# FPGA.net
KiCad netlist of a schematic drawn in Altium Designer
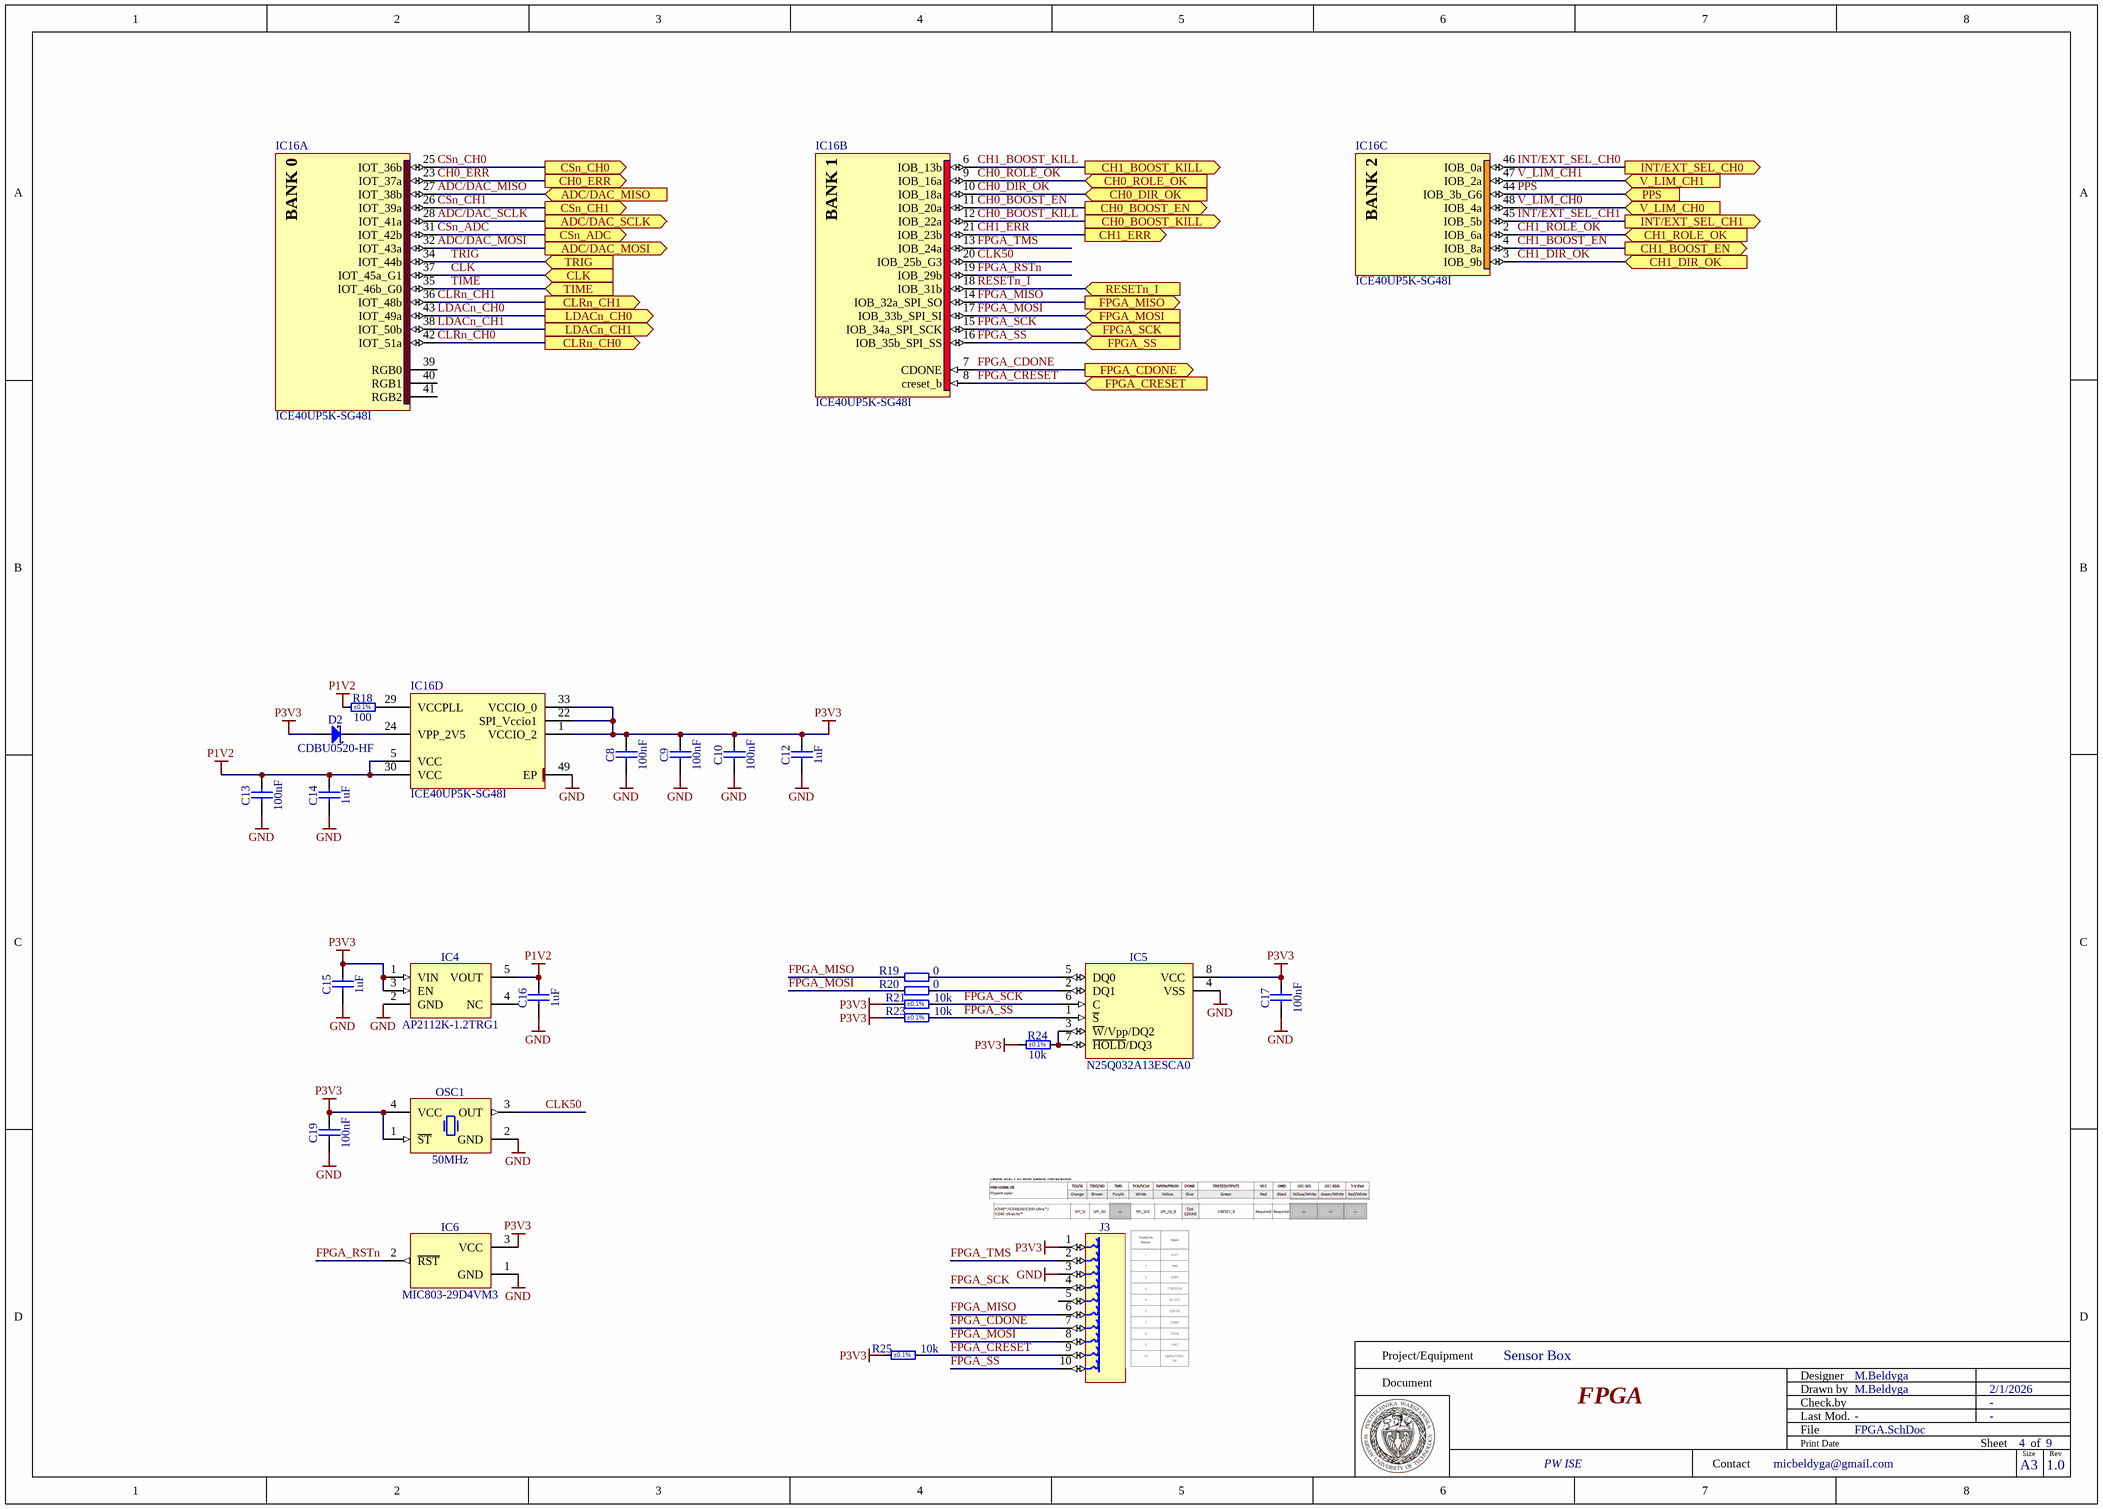
[diagram p0: FPGA.SchDoc]

(export (version "E")
  (design (tool "Eeschema 10.0.6"))
  (components
    (comp (ref "C8")
      (value "100nF")
      (footprint "CAPC1005X55N")
      (description "Non-polarised capacitor")
      (fields
        (field (name "PART NUMBER") "CC0402_100NF_16V_10%_X7R")
        (field (name "VOLTAGE") "16V")
        (field (name "AUTHOR") "CERN DEM JLC")
      )
      (libsource (lib "Capacitors") (part "Capacitor - non polarized"))
    )
    (comp (ref "C9")
      (value "100nF")
      (footprint "CAPC1005X55N")
      (description "Non-polarised capacitor")
      (fields
        (field (name "PART NUMBER") "CC0402_100NF_16V_10%_X7R")
        (field (name "VOLTAGE") "16V")
        (field (name "AUTHOR") "CERN DEM JLC")
      )
      (libsource (lib "Capacitors") (part "Capacitor - non polarized"))
    )
    (comp (ref "C10")
      (value "100nF")
      (footprint "CAPC1005X55N")
      (description "Non-polarised capacitor")
      (fields
        (field (name "PART NUMBER") "CC0402_100NF_16V_10%_X7R")
        (field (name "VOLTAGE") "16V")
        (field (name "AUTHOR") "CERN DEM JLC")
      )
      (libsource (lib "Capacitors") (part "Capacitor - non polarized"))
    )
    (comp (ref "C12")
      (value "1uF")
      (footprint "CAPC1005X55N")
      (description "Non-polarised capacitor")
      (fields
        (field (name "PART NUMBER") "CC0402_1UF_16V_10%_X5R")
        (field (name "VOLTAGE") "16V")
        (field (name "AUTHOR") "CERN DEM JLC")
      )
      (libsource (lib "Capacitors") (part "Capacitor - non polarized"))
    )
    (comp (ref "C13")
      (value "100nF")
      (footprint "CAPC1005X55N")
      (description "Non-polarised capacitor")
      (fields
        (field (name "PART NUMBER") "CC0402_100NF_16V_10%_X7R")
        (field (name "VOLTAGE") "16V")
        (field (name "AUTHOR") "CERN DEM JLC")
      )
      (libsource (lib "Capacitors") (part "Capacitor - non polarized"))
    )
    (comp (ref "C14")
      (value "1uF")
      (footprint "CAPC1005X55N")
      (description "Non-polarised capacitor")
      (fields
        (field (name "PART NUMBER") "CC0402_1UF_16V_10%_X5R")
        (field (name "VOLTAGE") "16V")
        (field (name "AUTHOR") "CERN DEM JLC")
      )
      (libsource (lib "Capacitors") (part "Capacitor - non polarized"))
    )
    (comp (ref "C15")
      (value "1uF")
      (footprint "CAPC1005X55N")
      (description "Non-polarised capacitor")
      (fields
        (field (name "PART NUMBER") "CC0402_1UF_16V_10%_X5R")
        (field (name "VOLTAGE") "16V")
        (field (name "AUTHOR") "CERN DEM JLC")
      )
      (libsource (lib "Capacitors") (part "Capacitor - non polarized"))
    )
    (comp (ref "C16")
      (value "1uF")
      (footprint "CAPC1005X55N")
      (description "Non-polarised capacitor")
      (fields
        (field (name "PART NUMBER") "CC0402_1UF_16V_10%_X5R")
        (field (name "VOLTAGE") "16V")
        (field (name "AUTHOR") "CERN DEM JLC")
      )
      (libsource (lib "Capacitors") (part "Capacitor - non polarized"))
    )
    (comp (ref "C17")
      (value "100nF")
      (footprint "CAPC1005X55N")
      (description "Non-polarised capacitor")
      (fields
        (field (name "PART NUMBER") "CC0402_100NF_16V_10%_X7R")
        (field (name "VOLTAGE") "16V")
        (field (name "AUTHOR") "CERN DEM JLC")
      )
      (libsource (lib "Capacitors") (part "Capacitor - non polarized"))
    )
    (comp (ref "C19")
      (value "100nF")
      (footprint "CAPC1005X55N")
      (description "Non-polarised capacitor")
      (fields
        (field (name "PART NUMBER") "CC0402_100NF_16V_10%_X7R")
        (field (name "VOLTAGE") "16V")
        (field (name "AUTHOR") "CERN DEM JLC")
      )
      (libsource (lib "Capacitors") (part "Capacitor - non polarized"))
    )
    (comp (ref "D2")
      (value "CDBU0520-HF")
      (footprint "SOD-523F")
      (description "Schottky Diode")
      (fields
        (field (name "VOLTAGE") "20V")
        (field (name "POWER") "500mA")
        (field (name "AUTHOR") "CERN DEM HF")
      )
      (libsource (lib "ICs And Semiconductors") (part "Diode Schottky"))
    )
    (comp (ref "IC4")
      (value "AP2112K-1.2TRG1")
      (footprint "SOT95P285X140-5N")
      (description "600mA CMOS Low Dropout Linear Regulator with Enable")
      (fields (field (name "MANUFACTURER") "DIODES INCORPORATED") (field (name "AUTHOR") "GK"))
      (libsource (lib "Regulators_SMPS") (part "REG_AP2112K-1.2"))
    )
    (comp (ref "IC5")
      (value "N25Q032A13ESCA0")
      (footprint "SOIC127P600X175-8N")
      (description "32Mb, 3V, Multiple I/O Serial Flash Memory")
      (fields (field (name "MANUFACTURER") "MICRON TECHNOLOGY") (field (name "AUTHOR") "CERN DEM HF"))
      (libsource (lib "ICs And Semiconductors") (part "N25Q032A13ESCA0"))
    )
    (comp (ref "IC6")
      (value "MIC803-29D4VM3")
      (footprint "SOT95P237X112-3N")
      (description "3.075V Microprocessor Supervisor Circuit With Open-Drain Reset Output")
      (fields (field (name "MANUFACTURER") "MICROCHIP TECHNOLOGY") (field (name "AUTHOR") "CERN DEM BC"))
      (libsource (lib "ICs And Semiconductors") (part "MIC803"))
    )
    (comp (ref "IC16")
      (value "ICE40UP5K-SG48I")
      (footprint "QFN50P700X700X100-49N-S550")
      (description "ICE40 Ultra FPGA, 3520 Logic Cells, 400 kHz Data Transfer Speed, 48 pin QFN")
      (fields (field (name "MANUFACTURER") "LATTICE SEMICONDUCTOR") (field (name "AUTHOR") "CERN DEM HF"))
      (libsource (lib "ICs And Semiconductors") (part "ICE40UP5K-SG48I"))
    )
    (comp (ref "J3")
      (value "TC2050-IDC")
      (footprint "TC2050-IDC")
      (description "TC2030-MCP and TC2050-IDC Pad Contact")
      (fields (field (name "AUTHOR") "CERN DEM HF"))
      (libsource (lib "Eletro-mechanical") (part "TC2050-IDC"))
    )
    (comp (ref "OSC1")
      (value "50MHz")
      (footprint "OSC_EPSON_SG-310")
      (description "Oscillator 4 pins 1=\\ST 2=GND 3=OUT 4=VCC")
      (fields
        (field (name "PART NUMBER") "OSC_50MHZ_EPSON_SG-310SCN")
        (field (name "MANUFACTURER") "EPSON TOYOCOM")
        (field (name "AUTHOR") "CERN DEM JLC")
      )
      (libsource (lib "ICs And Semiconductors") (part "Oscillator 1ST 2GND 3OUT 4VCC"))
    )
    (comp (ref "R18")
      (value "100")
      (footprint "RESC1005X35N")
      (description "Resistor - 0.1%")
      (fields
        (field (name "TOLERANCE") "±0.1%")
        (field (name "PART NUMBER") "R0402_100R_0.1%_0.063W_25PPM")
        (field (name "POWER") "0.063W")
        (field (name "AUTHOR") "CERN DEM JMW")
      )
      (libsource (lib "Resistors") (part "Resistor - 0.1%"))
    )
    (comp (ref "R19")
      (value "0")
      (footprint "RESC1005X40N")
      (description "Resistor")
      (fields
        (field (name "PART NUMBER") "R0402_0R_JUMPER")
        (field (name "MANUFACTURER") "GENERIC")
        (field (name "AUTHOR") "CERN DEM JLC")
      )
      (libsource (lib "Resistors") (part "Resistor"))
    )
    (comp (ref "R20")
      (value "0")
      (footprint "RESC1005X40N")
      (description "Resistor")
      (fields
        (field (name "PART NUMBER") "R0402_0R_JUMPER")
        (field (name "MANUFACTURER") "GENERIC")
        (field (name "AUTHOR") "CERN DEM JLC")
      )
      (libsource (lib "Resistors") (part "Resistor"))
    )
    (comp (ref "R21")
      (value "10k")
      (footprint "RESC1005X35N")
      (description "Resistor - 0.1%")
      (fields
        (field (name "TOLERANCE") "±0.1%")
        (field (name "PART NUMBER") "R0402_10K_0.1%_0.063W_25PPM")
        (field (name "POWER") "0.063W")
        (field (name "AUTHOR") "CERN DEM JMW")
      )
      (libsource (lib "Resistors") (part "Resistor - 0.1%"))
    )
    (comp (ref "R23")
      (value "10k")
      (footprint "RESC1005X35N")
      (description "Resistor - 0.1%")
      (fields
        (field (name "TOLERANCE") "±0.1%")
        (field (name "PART NUMBER") "R0402_10K_0.1%_0.063W_25PPM")
        (field (name "POWER") "0.063W")
        (field (name "AUTHOR") "CERN DEM JMW")
      )
      (libsource (lib "Resistors") (part "Resistor - 0.1%"))
    )
    (comp (ref "R24")
      (value "10k")
      (footprint "RESC1005X35N")
      (description "Resistor - 0.1%")
      (fields
        (field (name "TOLERANCE") "±0.1%")
        (field (name "PART NUMBER") "R0402_10K_0.1%_0.063W_25PPM")
        (field (name "POWER") "0.063W")
        (field (name "AUTHOR") "CERN DEM JMW")
      )
      (libsource (lib "Resistors") (part "Resistor - 0.1%"))
    )
    (comp (ref "R25")
      (value "10k")
      (footprint "RESC1005X35N")
      (description "Resistor - 0.1%")
      (fields
        (field (name "TOLERANCE") "±0.1%")
        (field (name "PART NUMBER") "R0402_10K_0.1%_0.063W_25PPM")
        (field (name "POWER") "0.063W")
        (field (name "AUTHOR") "CERN DEM JMW")
      )
      (libsource (lib "Resistors") (part "Resistor - 0.1%"))
    )
  )
  (nets
    (net (code "1") (name "/ADC{slash}DAC_MISO") (class "Default")
      (node (ref "IC16") (pin "27") (pinfunction "IOT_38b_27") (pintype "bidirectional"))
    )
    (net (code "2") (name "/ADC{slash}DAC_MOSI") (class "Default")
      (node (ref "IC16") (pin "32") (pinfunction "IOT_43a_32") (pintype "bidirectional"))
    )
    (net (code "3") (name "/ADC{slash}DAC_SCLK") (class "Default")
      (node (ref "IC16") (pin "28") (pinfunction "IOT_41a_28") (pintype "bidirectional"))
    )
    (net (code "4") (name "/CH0_BOOST_EN") (class "Default")
      (node (ref "IC16") (pin "11") (pinfunction "IOB_20a_11") (pintype "bidirectional"))
    )
    (net (code "5") (name "/CH0_BOOST_KILL") (class "Default")
      (node (ref "IC16") (pin "12") (pinfunction "IOB_22a_12") (pintype "bidirectional"))
    )
    (net (code "6") (name "/CH0_DIR_OK") (class "Default")
      (node (ref "IC16") (pin "10") (pinfunction "IOB_18a_10") (pintype "bidirectional"))
    )
    (net (code "7") (name "/CH0_ERR") (class "Default")
      (node (ref "IC16") (pin "23") (pinfunction "IOT_37a_23") (pintype "bidirectional"))
    )
    (net (code "8") (name "/CH0_ROLE_OK") (class "Default")
      (node (ref "IC16") (pin "9") (pinfunction "IOB_16a_9") (pintype "bidirectional"))
    )
    (net (code "9") (name "/CH1_BOOST_EN") (class "Default")
      (node (ref "IC16") (pin "4") (pinfunction "IOB_8a_4") (pintype "bidirectional"))
    )
    (net (code "10") (name "/CH1_BOOST_KILL") (class "Default")
      (node (ref "IC16") (pin "6") (pinfunction "IOB_13b_6") (pintype "bidirectional"))
    )
    (net (code "11") (name "/CH1_DIR_OK") (class "Default")
      (node (ref "IC16") (pin "3") (pinfunction "IOB_9b_3") (pintype "bidirectional"))
    )
    (net (code "12") (name "/CH1_ERR") (class "Default")
      (node (ref "IC16") (pin "21") (pinfunction "IOB_23b_21") (pintype "bidirectional"))
    )
    (net (code "13") (name "/CH1_ROLE_OK") (class "Default")
      (node (ref "IC16") (pin "2") (pinfunction "IOB_6a_2") (pintype "bidirectional"))
    )
    (net (code "14") (name "/CLK") (class "Default")
      (node (ref "IC16") (pin "37") (pinfunction "IOT_45a_G1_37") (pintype "bidirectional"))
    )
    (net (code "15") (name "/CLK50") (class "Default")
      (node (ref "IC16") (pin "20") (pinfunction "IOB_25b_G3_20") (pintype "bidirectional"))
      (node (ref "OSC1") (pin "3") (pinfunction "OUT_3") (pintype "output"))
    )
    (net (code "16") (name "/CLRn_CH0") (class "Default")
      (node (ref "IC16") (pin "42") (pinfunction "IOT_51a_42") (pintype "bidirectional"))
    )
    (net (code "17") (name "/CLRn_CH1") (class "Default")
      (node (ref "IC16") (pin "36") (pinfunction "IOT_48b_36") (pintype "bidirectional"))
    )
    (net (code "18") (name "/CSn_ADC") (class "Default")
      (node (ref "IC16") (pin "31") (pinfunction "IOT_42b_31") (pintype "bidirectional"))
    )
    (net (code "19") (name "/CSn_CH0") (class "Default")
      (node (ref "IC16") (pin "25") (pinfunction "IOT_36b_25") (pintype "bidirectional"))
    )
    (net (code "20") (name "/CSn_CH1") (class "Default")
      (node (ref "IC16") (pin "26") (pinfunction "IOT_39a_26") (pintype "bidirectional"))
    )
    (net (code "21") (name "/FPGA_CDONE") (class "Default")
      (node (ref "IC16") (pin "7") (pinfunction "CDONE_7") (pintype "input"))
      (node (ref "J3") (pin "7") (pinfunction "7_7") (pintype "bidirectional"))
    )
    (net (code "22") (name "/FPGA_CRESET") (class "Default")
      (node (ref "IC16") (pin "8") (pinfunction "creset_b_8") (pintype "input"))
      (node (ref "J3") (pin "9") (pinfunction "9_9") (pintype "bidirectional"))
      (node (ref "R25") (pin "2") (pinfunction "2_2") (pintype "passive"))
    )
    (net (code "23") (name "/FPGA_MISO") (class "Default")
      (node (ref "IC16") (pin "14") (pinfunction "IOB_32a_SPI_SO_14") (pintype "bidirectional"))
      (node (ref "J3") (pin "6") (pinfunction "6_6") (pintype "bidirectional"))
      (node (ref "R19") (pin "1") (pinfunction "1_1") (pintype "passive"))
    )
    (net (code "24") (name "/FPGA_MOSI") (class "Default")
      (node (ref "IC16") (pin "17") (pinfunction "IOB_33b_SPI_SI_17") (pintype "bidirectional"))
      (node (ref "J3") (pin "8") (pinfunction "8_8") (pintype "bidirectional"))
      (node (ref "R20") (pin "1") (pinfunction "1_1") (pintype "passive"))
    )
    (net (code "25") (name "/FPGA_RSTn") (class "Default")
      (node (ref "IC16") (pin "19") (pinfunction "IOB_29b_19") (pintype "bidirectional"))
      (node (ref "IC6") (pin "2") (pinfunction "~{RST}_2") (pintype "output"))
    )
    (net (code "26") (name "/FPGA_SCK") (class "Default")
      (node (ref "IC16") (pin "15") (pinfunction "IOB_34a_SPI_SCK_15") (pintype "bidirectional"))
      (node (ref "IC5") (pin "6") (pinfunction "C_6") (pintype "input"))
      (node (ref "J3") (pin "4") (pinfunction "4_4") (pintype "bidirectional"))
      (node (ref "R21") (pin "2") (pinfunction "2_2") (pintype "passive"))
    )
    (net (code "27") (name "/FPGA_SS") (class "Default")
      (node (ref "IC16") (pin "16") (pinfunction "IOB_35b_SPI_SS_16") (pintype "bidirectional"))
      (node (ref "IC5") (pin "1") (pinfunction "~{S}_1") (pintype "input"))
      (node (ref "J3") (pin "10") (pinfunction "10_10") (pintype "bidirectional"))
      (node (ref "R23") (pin "2") (pinfunction "2_2") (pintype "passive"))
    )
    (net (code "28") (name "/FPGA_TMS") (class "Default")
      (node (ref "IC16") (pin "13") (pinfunction "IOB_24a_13") (pintype "bidirectional"))
      (node (ref "J3") (pin "2") (pinfunction "2_2") (pintype "bidirectional"))
    )
    (net (code "29") (name "/INT{slash}EXT_SEL_CH0") (class "Default")
      (node (ref "IC16") (pin "46") (pinfunction "IOB_0a_46") (pintype "bidirectional"))
    )
    (net (code "30") (name "/INT{slash}EXT_SEL_CH1") (class "Default")
      (node (ref "IC16") (pin "45") (pinfunction "IOB_5b_45") (pintype "bidirectional"))
    )
    (net (code "31") (name "/LDACn_CH0") (class "Default")
      (node (ref "IC16") (pin "43") (pinfunction "IOT_49a_43") (pintype "bidirectional"))
    )
    (net (code "32") (name "/LDACn_CH1") (class "Default")
      (node (ref "IC16") (pin "38") (pinfunction "IOT_50b_38") (pintype "bidirectional"))
    )
    (net (code "33") (name "/PPS") (class "Default")
      (node (ref "IC16") (pin "44") (pinfunction "IOB_3b_G6_44") (pintype "bidirectional"))
    )
    (net (code "34") (name "/RESETn_I") (class "Default")
      (node (ref "IC16") (pin "18") (pinfunction "IOB_31b_18") (pintype "bidirectional"))
    )
    (net (code "35") (name "/TIME") (class "Default")
      (node (ref "IC16") (pin "35") (pinfunction "IOT_46b_G0_35") (pintype "bidirectional"))
    )
    (net (code "36") (name "/TRIG") (class "Default")
      (node (ref "IC16") (pin "34") (pinfunction "IOT_44b_34") (pintype "bidirectional"))
    )
    (net (code "37") (name "/V_LIM_CH0") (class "Default")
      (node (ref "IC16") (pin "48") (pinfunction "IOB_4a_48") (pintype "bidirectional"))
    )
    (net (code "38") (name "/V_LIM_CH1") (class "Default")
      (node (ref "IC16") (pin "47") (pinfunction "IOB_2a_47") (pintype "bidirectional"))
    )
    (net (code "39") (name "GND") (class "Default")
      (node (ref "C10") (pin "1") (pinfunction "1_1") (pintype "passive"))
      (node (ref "C12") (pin "1") (pinfunction "1_1") (pintype "passive"))
      (node (ref "C13") (pin "1") (pinfunction "1_1") (pintype "passive"))
      (node (ref "C14") (pin "1") (pinfunction "1_1") (pintype "passive"))
      (node (ref "C15") (pin "1") (pinfunction "1_1") (pintype "passive"))
      (node (ref "C16") (pin "1") (pinfunction "1_1") (pintype "passive"))
      (node (ref "C17") (pin "1") (pinfunction "1_1") (pintype "passive"))
      (node (ref "C19") (pin "1") (pinfunction "1_1") (pintype "passive"))
      (node (ref "C8") (pin "1") (pinfunction "1_1") (pintype "passive"))
      (node (ref "C9") (pin "1") (pinfunction "1_1") (pintype "passive"))
      (node (ref "IC16") (pin "49") (pinfunction "EP_49") (pintype "power_in"))
      (node (ref "IC4") (pin "2") (pinfunction "GND_2") (pintype "power_in"))
      (node (ref "IC5") (pin "4") (pinfunction "VSS_4") (pintype "power_in"))
      (node (ref "IC6") (pin "1") (pinfunction "GND_1") (pintype "power_in"))
      (node (ref "J3") (pin "3") (pinfunction "3_3") (pintype "bidirectional"))
      (node (ref "OSC1") (pin "2") (pinfunction "GND_2") (pintype "power_in"))
    )
    (net (code "40") (name "Net-(D2-C)") (class "Default")
      (node (ref "D2") (pin "1") (pinfunction "C_1") (pintype "passive"))
      (node (ref "IC16") (pin "24") (pinfunction "VPP_2V5_24") (pintype "power_in"))
    )
    (net (code "41") (name "Net-(IC5-DQ0)") (class "Default")
      (node (ref "IC5") (pin "5") (pinfunction "DQ0_5") (pintype "bidirectional"))
      (node (ref "R19") (pin "2") (pinfunction "2_2") (pintype "passive"))
    )
    (net (code "42") (name "Net-(IC5-DQ1)") (class "Default")
      (node (ref "IC5") (pin "2") (pinfunction "DQ1_2") (pintype "bidirectional"))
      (node (ref "R20") (pin "2") (pinfunction "2_2") (pintype "passive"))
    )
    (net (code "43") (name "Net-(IC5-~{HOLD}{slash}DQ3)") (class "Default")
      (node (ref "IC5") (pin "3") (pinfunction "~{W}/Vpp/DQ2_3") (pintype "bidirectional"))
      (node (ref "IC5") (pin "7") (pinfunction "~{HOLD}/DQ3_7") (pintype "bidirectional"))
      (node (ref "R24") (pin "2") (pinfunction "2_2") (pintype "passive"))
    )
    (net (code "44") (name "Net-(IC16D-VCCPLL)") (class "Default")
      (node (ref "IC16") (pin "29") (pinfunction "VCCPLL_29") (pintype "power_in"))
      (node (ref "R18") (pin "2") (pinfunction "2_2") (pintype "passive"))
    )
    (net (code "45") (name "P1V2") (class "Default")
      (node (ref "C13") (pin "2") (pinfunction "2_2") (pintype "passive"))
      (node (ref "C14") (pin "2") (pinfunction "2_2") (pintype "passive"))
      (node (ref "C16") (pin "2") (pinfunction "2_2") (pintype "passive"))
      (node (ref "IC16") (pin "30") (pinfunction "VCC_30") (pintype "power_in"))
      (node (ref "IC16") (pin "5") (pinfunction "VCC_5") (pintype "power_in"))
      (node (ref "IC4") (pin "5") (pinfunction "VOUT_5") (pintype "power_in"))
      (node (ref "R18") (pin "1") (pinfunction "1_1") (pintype "passive"))
    )
    (net (code "46") (name "P3V3") (class "Default")
      (node (ref "C10") (pin "2") (pinfunction "2_2") (pintype "passive"))
      (node (ref "C12") (pin "2") (pinfunction "2_2") (pintype "passive"))
      (node (ref "C15") (pin "2") (pinfunction "2_2") (pintype "passive"))
      (node (ref "C17") (pin "2") (pinfunction "2_2") (pintype "passive"))
      (node (ref "C19") (pin "2") (pinfunction "2_2") (pintype "passive"))
      (node (ref "C8") (pin "2") (pinfunction "2_2") (pintype "passive"))
      (node (ref "C9") (pin "2") (pinfunction "2_2") (pintype "passive"))
      (node (ref "D2") (pin "2") (pinfunction "A_2") (pintype "passive"))
      (node (ref "IC16") (pin "1") (pinfunction "VCCIO_2_1") (pintype "power_in"))
      (node (ref "IC16") (pin "22") (pinfunction "SPI_Vccio1_22") (pintype "power_in"))
      (node (ref "IC16") (pin "33") (pinfunction "VCCIO_0_33") (pintype "power_in"))
      (node (ref "IC4") (pin "1") (pinfunction "VIN_1") (pintype "input"))
      (node (ref "IC4") (pin "3") (pinfunction "EN_3") (pintype "input"))
      (node (ref "IC5") (pin "8") (pinfunction "VCC_8") (pintype "power_in"))
      (node (ref "IC6") (pin "3") (pinfunction "VCC_3") (pintype "power_in"))
      (node (ref "J3") (pin "1") (pinfunction "1_1") (pintype "bidirectional"))
      (node (ref "OSC1") (pin "1") (pinfunction "ST_1") (pintype "input"))
      (node (ref "OSC1") (pin "4") (pinfunction "VCC_4") (pintype "power_in"))
      (node (ref "R21") (pin "1") (pinfunction "1_1") (pintype "passive"))
      (node (ref "R23") (pin "1") (pinfunction "1_1") (pintype "passive"))
      (node (ref "R24") (pin "1") (pinfunction "1_1") (pintype "passive"))
      (node (ref "R25") (pin "1") (pinfunction "1_1") (pintype "passive"))
    )
    (net (code "47") (name "unconnected-(IC4-NC-Pad4)") (class "Default")
      (node (ref "IC4") (pin "4") (pinfunction "NC_4") (pintype "passive"))
    )
    (net (code "48") (name "unconnected-(IC16A-RGB0-Pad39)") (class "Default")
      (node (ref "IC16") (pin "39") (pinfunction "RGB0_39") (pintype "power_in"))
    )
    (net (code "49") (name "unconnected-(IC16A-RGB1-Pad40)") (class "Default")
      (node (ref "IC16") (pin "40") (pinfunction "RGB1_40") (pintype "power_in"))
    )
    (net (code "50") (name "unconnected-(IC16A-RGB2-Pad41)") (class "Default")
      (node (ref "IC16") (pin "41") (pinfunction "RGB2_41") (pintype "power_in"))
    )
    (net (code "51") (name "unconnected-(J3-Pad5)") (class "Default")
      (node (ref "J3") (pin "5") (pinfunction "5_5") (pintype "bidirectional"))
    )
  )
)
